# SparkFun_Qwiic_Micro_SAMD21E.net
KiCad netlist of a schematic drawn in EAGLE
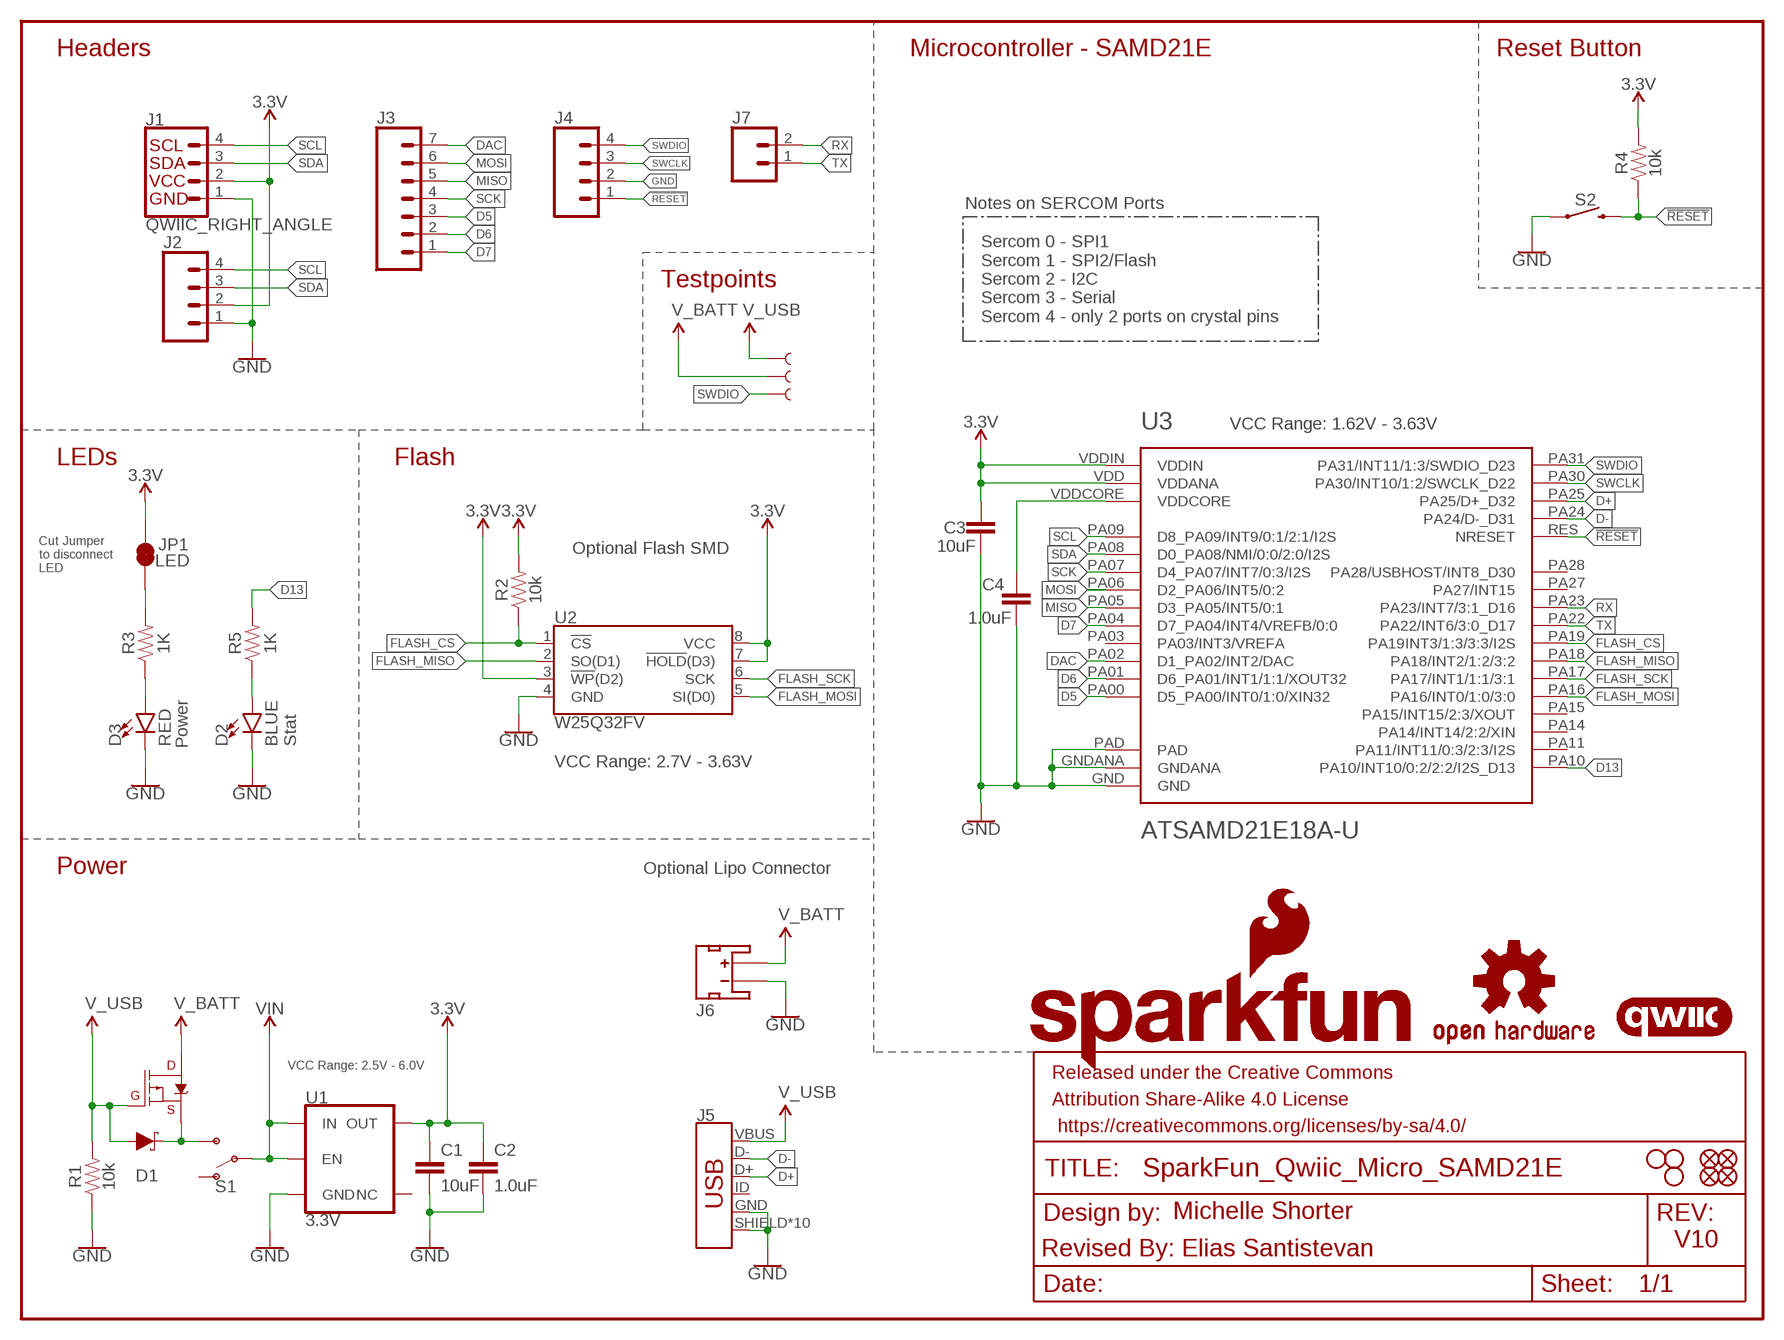
[diagram p0: schematic, sheet 1]

(export (version "E")
  (design (tool "Eeschema 10.0.6"))
  (components
    (comp (ref "C1")
      (value "10uF")
      (footprint "eagle-import:0603")
      (libsource (lib "eagle-import") (part "10UF-0603-6.3V-20%"))
    )
    (comp (ref "C2")
      (value "1.0uF")
      (footprint "eagle-import:0402")
      (libsource (lib "eagle-import") (part "1.0UF-0402-16V-10%"))
    )
    (comp (ref "C3")
      (value "10uF")
      (footprint "eagle-import:0603")
      (libsource (lib "eagle-import") (part "10UF-0603-6.3V-20%"))
    )
    (comp (ref "C4")
      (value "1.0uF")
      (footprint "eagle-import:0402")
      (libsource (lib "eagle-import") (part "1.0UF-0402-16V-10%"))
    )
    (comp (ref "D1")
      (value "1A/23V/620mV")
      (footprint "eagle-import:SOD-323")
      (libsource (lib "eagle-import") (part "DIODE-SCHOTTKY-BAT20J"))
    )
    (comp (ref "D2")
      (value "BLUE")
      (footprint "eagle-import:LED-0603")
      (libsource (lib "eagle-import") (part "LED-BLUE0603"))
    )
    (comp (ref "D3")
      (value "RED")
      (footprint "eagle-import:LED-0603")
      (libsource (lib "eagle-import") (part "LED-RED0603"))
    )
    (comp (ref "FD1")
      (value "FIDUCIALUFIDUCIAL")
      (footprint "eagle-import:FIDUCIAL-MICRO")
      (libsource (lib "eagle-import") (part "FIDUCIALUFIDUCIAL"))
    )
    (comp (ref "FD2")
      (value "FIDUCIALUFIDUCIAL")
      (footprint "eagle-import:FIDUCIAL-MICRO")
      (libsource (lib "eagle-import") (part "FIDUCIALUFIDUCIAL"))
    )
    (comp (ref "FD3")
      (value "FIDUCIALUFIDUCIAL")
      (footprint "eagle-import:FIDUCIAL-MICRO")
      (libsource (lib "eagle-import") (part "FIDUCIALUFIDUCIAL"))
    )
    (comp (ref "FD4")
      (value "FIDUCIALUFIDUCIAL")
      (footprint "eagle-import:FIDUCIAL-MICRO")
      (libsource (lib "eagle-import") (part "FIDUCIALUFIDUCIAL"))
    )
    (comp (ref "FRAME1")
      (value "FRAME-LETTER")
      (footprint "eagle-import:CREATIVE_COMMONS")
      (libsource (lib "eagle-import") (part "FRAME-LETTER"))
    )
    (comp (ref "H1")
      (value "STAND-OFF")
      (footprint "eagle-import:STAND-OFF")
      (libsource (lib "eagle-import") (part "STAND-OFF"))
    )
    (comp (ref "H2")
      (value "STAND-OFF")
      (footprint "eagle-import:STAND-OFF")
      (libsource (lib "eagle-import") (part "STAND-OFF"))
    )
    (comp (ref "H3")
      (value "STAND-OFF")
      (footprint "eagle-import:STAND-OFF")
      (libsource (lib "eagle-import") (part "STAND-OFF"))
    )
    (comp (ref "J1")
      (value "QWIIC_RIGHT_ANGLE")
      (footprint "eagle-import:JST04_1MM_RA")
      (libsource (lib "eagle-import") (part "QWIIC_CONNECTORJS-1MM"))
    )
    (comp (ref "J2")
      (value "CONN_041X04_NO_SILK")
      (footprint "eagle-import:1X04_NO_SILK")
      (libsource (lib "eagle-import") (part "CONN_041X04_NO_SILK"))
    )
    (comp (ref "J3")
      (value "CONN_07NO_SILK")
      (footprint "eagle-import:1X07_NO_SILK")
      (libsource (lib "eagle-import") (part "CONN_07NO_SILK"))
    )
    (comp (ref "J4")
      (value "CONN_041.27MM_NO_SILK")
      (footprint "eagle-import:1X04_1.27MM_NO_SILK")
      (libsource (lib "eagle-import") (part "CONN_041.27MM_NO_SILK"))
    )
    (comp (ref "J5")
      (value "USB_MICRO-B_HALF_PTH_MILL")
      (footprint "eagle-import:USB-MICROB-PTH-MILL")
      (libsource (lib "eagle-import") (part "USB_MICRO-B_HALF_PTH_MILL"))
    )
    (comp (ref "J6")
      (value "JST_2MM_MALE")
      (footprint "eagle-import:JST-2-SMD")
      (libsource (lib "eagle-import") (part "JST_2MM_MALE"))
    )
    (comp (ref "J7")
      (value "CONN_021X02_NO_SILK")
      (footprint "eagle-import:1X02_NO_SILK")
      (libsource (lib "eagle-import") (part "CONN_021X02_NO_SILK"))
    )
    (comp (ref "JP1")
      (value "LED")
      (footprint "eagle-import:SMT-JUMPER_2_NC_TRACE_SILK")
      (libsource (lib "eagle-import") (part "JUMPER-SMT_2_NC_TRACE_SILK"))
    )
    (comp (ref "LOGO1")
      (value "SFE_LOGO_NAME.1_INCH")
      (footprint "eagle-import:SFE_LOGO_NAME_.1")
      (libsource (lib "eagle-import") (part "SFE_LOGO_NAME.1_INCH"))
    )
    (comp (ref "LOGO2")
      (value "SFE_LOGO_FLAME.2_INCH")
      (footprint "eagle-import:SFE_LOGO_FLAME_.2")
      (libsource (lib "eagle-import") (part "SFE_LOGO_FLAME.2_INCH"))
    )
    (comp (ref "LOGO3")
      (value "OSHW-LOGOS")
      (footprint "eagle-import:OSHW-LOGO-S")
      (libsource (lib "eagle-import") (part "OSHW-LOGOS"))
    )
    (comp (ref "LOGO4")
      (value "QWIIC_LOGO_3MM")
      (footprint "eagle-import:QWIIC_3MM")
      (libsource (lib "eagle-import") (part "QWIIC_LOGO_3MM"))
    )
    (comp (ref "Q1")
      (value "3.1A/30V/105mΩ")
      (footprint "eagle-import:SOT23-3")
      (libsource (lib "eagle-import") (part "MOSFET_PCH-DMG2307L"))
    )
    (comp (ref "R1")
      (value "10k")
      (footprint "eagle-import:0402")
      (libsource (lib "eagle-import") (part "10KOHM-0402-1/16W-1%"))
    )
    (comp (ref "R2")
      (value "10k")
      (footprint "eagle-import:0402")
      (libsource (lib "eagle-import") (part "10KOHM-0402-1/16W-1%"))
    )
    (comp (ref "R3")
      (value "1K")
      (footprint "eagle-import:0402")
      (libsource (lib "eagle-import") (part "1KOHM-0402-1/16W-1%"))
    )
    (comp (ref "R4")
      (value "10k")
      (footprint "eagle-import:0402")
      (libsource (lib "eagle-import") (part "10KOHM-0402-1/16W-1%"))
    )
    (comp (ref "R5")
      (value "1K")
      (footprint "eagle-import:0402")
      (libsource (lib "eagle-import") (part "1KOHM-0402-1/16W-1%"))
    )
    (comp (ref "S1")
      (value "SWITCH-SPDT-SMD-RIGHT-ANGLE")
      (footprint "eagle-import:SWITCH_SPST_SMD_A")
      (libsource (lib "eagle-import") (part "SWITCH-SPDT-SMD-RIGHT-ANGLE"))
    )
    (comp (ref "S2")
      (value "MOMENTARY-SWITCH-SPST-SMD-4.6X2.8MM")
      (footprint "eagle-import:TACTILE_SWITCH_SMD_4.6X2.8MM")
      (libsource (lib "eagle-import") (part "MOMENTARY-SWITCH-SPST-SMD-4.6X2.8MM"))
    )
    (comp (ref "TP1")
      (value "TEST-POINTTP_15TH_THRU")
      (footprint "eagle-import:TP_15TH")
      (libsource (lib "eagle-import") (part "TEST-POINTTP_15TH_THRU"))
    )
    (comp (ref "TP2")
      (value "TEST-POINTTP_15TH_THRU")
      (footprint "eagle-import:TP_15TH")
      (libsource (lib "eagle-import") (part "TEST-POINTTP_15TH_THRU"))
    )
    (comp (ref "TP3")
      (value "TEST-POINTTP_15TH_THRU")
      (footprint "eagle-import:TP_15TH")
      (libsource (lib "eagle-import") (part "TEST-POINTTP_15TH_THRU"))
    )
    (comp (ref "U1")
      (value "3.3V")
      (footprint "eagle-import:SOT23-5")
      (libsource (lib "eagle-import") (part "V_REG_AP2112K-3.3V"))
    )
    (comp (ref "U2")
      (value "W25Q32FV")
      (footprint "eagle-import:SOIC-8")
      (libsource (lib "eagle-import") (part "W25Q32FVSS"))
    )
    (comp (ref "U3")
      (value "ATSAMD21E18A-U")
      (footprint "eagle-import:QFN-32_SAMD")
      (libsource (lib "eagle-import") (part "ATSAMD21E18A-U"))
    )
  )
  (nets
    (net (code "1") (name "/~{RESET}") (class "Default")
      (node (ref "J4") (pin "1") (pinfunction "1_1") (pintype "passive"))
      (node (ref "R4") (pin "1") (pinfunction "1_1") (pintype "passive"))
      (node (ref "S2") (pin "3") (pinfunction "2_3") (pintype "passive"))
      (node (ref "S2") (pin "4") (pinfunction "2_4") (pintype "passive"))
      (node (ref "U3") (pin "RES") (pinfunction "NRESET_RES") (pintype "bidirectional"))
    )
    (net (code "2") (name "3.3V") (class "Default")
      (node (ref "C1") (pin "1") (pinfunction "1_1") (pintype "passive"))
      (node (ref "C2") (pin "1") (pinfunction "1_1") (pintype "passive"))
      (node (ref "C3") (pin "1") (pinfunction "1_1") (pintype "passive"))
      (node (ref "J1") (pin "2") (pinfunction "2_2") (pintype "power_in"))
      (node (ref "J2") (pin "2") (pinfunction "2_2") (pintype "passive"))
      (node (ref "JP1") (pin "2") (pinfunction "2_2") (pintype "passive"))
      (node (ref "R2") (pin "2") (pinfunction "2_2") (pintype "passive"))
      (node (ref "R4") (pin "2") (pinfunction "2_2") (pintype "passive"))
      (node (ref "U1") (pin "5") (pinfunction "OUT_5") (pintype "passive"))
      (node (ref "U2") (pin "3") (pinfunction "~{WP}(D2)_3") (pintype "bidirectional"))
      (node (ref "U2") (pin "7") (pinfunction "~{HOLD}(D3)_7") (pintype "bidirectional"))
      (node (ref "U2") (pin "8") (pinfunction "VCC_8") (pintype "bidirectional"))
      (node (ref "U3") (pin "VDD") (pinfunction "VDDANA_VDD") (pintype "power_in"))
      (node (ref "U3") (pin "VDDIN") (pinfunction "VDDIN_VDDIN") (pintype "power_in"))
    )
    (net (code "3") (name "D+") (class "Default")
      (node (ref "J5") (pin "D+") (pinfunction "D+_D+") (pintype "bidirectional"))
      (node (ref "U3") (pin "PA25") (pinfunction "PA25/D+_D32_PA25") (pintype "bidirectional"))
    )
    (net (code "4") (name "D-") (class "Default")
      (node (ref "J5") (pin "D-") (pinfunction "D-_D-") (pintype "bidirectional"))
      (node (ref "U3") (pin "PA24") (pinfunction "PA24/D-_D31_PA24") (pintype "bidirectional"))
    )
    (net (code "5") (name "D5") (class "Default")
      (node (ref "J3") (pin "3") (pinfunction "3_3") (pintype "passive"))
      (node (ref "U3") (pin "PA00") (pinfunction "D5_PA00/INT0/1:0/XIN32_PA00") (pintype "bidirectional"))
    )
    (net (code "6") (name "D6") (class "Default")
      (node (ref "J3") (pin "2") (pinfunction "2_2") (pintype "passive"))
      (node (ref "U3") (pin "PA01") (pinfunction "D6_PA01/INT1/1:1/XOUT32_PA01") (pintype "bidirectional"))
    )
    (net (code "7") (name "D7") (class "Default")
      (node (ref "J3") (pin "1") (pinfunction "1_1") (pintype "passive"))
      (node (ref "U3") (pin "PA04") (pinfunction "D7_PA04/INT4/VREFB/0:0_PA04") (pintype "bidirectional"))
    )
    (net (code "8") (name "D13") (class "Default")
      (node (ref "R5") (pin "2") (pinfunction "2_2") (pintype "passive"))
      (node (ref "U3") (pin "PA10") (pinfunction "PA10/INT10/0:2/2:2/I2S_D13_PA10") (pintype "bidirectional"))
    )
    (net (code "9") (name "DAC") (class "Default")
      (node (ref "J3") (pin "7") (pinfunction "7_7") (pintype "passive"))
      (node (ref "U3") (pin "PA02") (pinfunction "D1_PA02/INT2/DAC_PA02") (pintype "bidirectional"))
    )
    (net (code "10") (name "FLASH_CS") (class "Default")
      (node (ref "R2") (pin "1") (pinfunction "1_1") (pintype "passive"))
      (node (ref "U2") (pin "1") (pinfunction "~{CS}_1") (pintype "bidirectional"))
      (node (ref "U3") (pin "PA19") (pinfunction "PA19INT3/1:3/3:3/I2S_PA19") (pintype "bidirectional"))
    )
    (net (code "11") (name "FLASH_MISO") (class "Default")
      (node (ref "U2") (pin "2") (pinfunction "SO(D1)_2") (pintype "bidirectional"))
      (node (ref "U3") (pin "PA18") (pinfunction "PA18/INT2/1:2/3:2_PA18") (pintype "bidirectional"))
    )
    (net (code "12") (name "FLASH_MOSI") (class "Default")
      (node (ref "U2") (pin "5") (pinfunction "SI(D0)_5") (pintype "bidirectional"))
      (node (ref "U3") (pin "PA16") (pinfunction "PA16/INT0/1:0/3:0_PA16") (pintype "bidirectional"))
    )
    (net (code "13") (name "FLASH_SCK") (class "Default")
      (node (ref "U2") (pin "6") (pinfunction "SCK_6") (pintype "bidirectional"))
      (node (ref "U3") (pin "PA17") (pinfunction "PA17/INT1/1:1/3:1_PA17") (pintype "bidirectional"))
    )
    (net (code "14") (name "GND") (class "Default")
      (node (ref "C1") (pin "2") (pinfunction "2_2") (pintype "passive"))
      (node (ref "C2") (pin "2") (pinfunction "2_2") (pintype "passive"))
      (node (ref "C3") (pin "2") (pinfunction "2_2") (pintype "passive"))
      (node (ref "C4") (pin "1") (pinfunction "1_1") (pintype "passive"))
      (node (ref "D2") (pin "C") (pinfunction "C_C") (pintype "passive"))
      (node (ref "D3") (pin "C") (pinfunction "C_C") (pintype "passive"))
      (node (ref "J1") (pin "1") (pinfunction "1_1") (pintype "power_in"))
      (node (ref "J2") (pin "1") (pinfunction "1_1") (pintype "passive"))
      (node (ref "J4") (pin "2") (pinfunction "2_2") (pintype "passive"))
      (node (ref "J5") (pin "GND") (pinfunction "GND_GND") (pintype "power_in"))
      (node (ref "J5") (pin "SHIELD") (pinfunction "SHIELD_SHIELD") (pintype "bidirectional"))
      (node (ref "J5") (pin "SHIELD10") (pinfunction "SHIELD_SHIELD10") (pintype "bidirectional"))
      (node (ref "J5") (pin "SHIELD2") (pinfunction "SHIELD_SHIELD2") (pintype "bidirectional"))
      (node (ref "J5") (pin "SHIELD3") (pinfunction "SHIELD_SHIELD3") (pintype "bidirectional"))
      (node (ref "J5") (pin "SHIELD4") (pinfunction "SHIELD_SHIELD4") (pintype "bidirectional"))
      (node (ref "J5") (pin "SHIELD5") (pinfunction "SHIELD_SHIELD5") (pintype "bidirectional"))
      (node (ref "J5") (pin "SHIELD6") (pinfunction "SHIELD_SHIELD6") (pintype "bidirectional"))
      (node (ref "J5") (pin "SHIELD7") (pinfunction "SHIELD_SHIELD7") (pintype "bidirectional"))
      (node (ref "J5") (pin "SHIELD8") (pinfunction "SHIELD_SHIELD8") (pintype "bidirectional"))
      (node (ref "J5") (pin "SHIELD9") (pinfunction "SHIELD_SHIELD9") (pintype "bidirectional"))
      (node (ref "J6") (pin "1") (pinfunction "-_1") (pintype "bidirectional"))
      (node (ref "R1") (pin "1") (pinfunction "1_1") (pintype "passive"))
      (node (ref "S2") (pin "1") (pinfunction "1_1") (pintype "passive"))
      (node (ref "S2") (pin "2") (pinfunction "1_2") (pintype "passive"))
      (node (ref "U1") (pin "2") (pinfunction "GND_2") (pintype "input"))
      (node (ref "U2") (pin "4") (pinfunction "GND_4") (pintype "bidirectional"))
      (node (ref "U3") (pin "GND") (pinfunction "GND_GND") (pintype "power_in"))
      (node (ref "U3") (pin "GNDANA") (pinfunction "GNDANA_GNDANA") (pintype "power_in"))
      (node (ref "U3") (pin "PAD") (pinfunction "PAD_PAD") (pintype "power_in"))
    )
    (net (code "15") (name "MISO") (class "Default")
      (node (ref "J3") (pin "5") (pinfunction "5_5") (pintype "passive"))
      (node (ref "U3") (pin "PA05") (pinfunction "D3_PA05/INT5/0:1_PA05") (pintype "bidirectional"))
    )
    (net (code "16") (name "MOSI") (class "Default")
      (node (ref "J3") (pin "6") (pinfunction "6_6") (pintype "passive"))
      (node (ref "U3") (pin "PA06") (pinfunction "D2_PA06/INT5/0:2_PA06") (pintype "bidirectional"))
    )
    (net (code "17") (name "Net-(C4-Pad2)") (class "Default")
      (node (ref "C4") (pin "2") (pinfunction "2_2") (pintype "passive"))
      (node (ref "U3") (pin "VDDCORE") (pinfunction "VDDCORE_VDDCORE") (pintype "power_in"))
    )
    (net (code "18") (name "Net-(D2-PadA)") (class "Default")
      (node (ref "D2") (pin "A") (pinfunction "A_A") (pintype "passive"))
      (node (ref "R5") (pin "1") (pinfunction "1_1") (pintype "passive"))
    )
    (net (code "19") (name "Net-(D3-PadA)") (class "Default")
      (node (ref "D3") (pin "A") (pinfunction "A_A") (pintype "passive"))
      (node (ref "R3") (pin "1") (pinfunction "1_1") (pintype "passive"))
    )
    (net (code "20") (name "Net-(JP1-Pad1)") (class "Default")
      (node (ref "JP1") (pin "1") (pinfunction "1_1") (pintype "passive"))
      (node (ref "R3") (pin "2") (pinfunction "2_2") (pintype "passive"))
    )
    (net (code "21") (name "Net-(Q1-S)") (class "Default")
      (node (ref "D1") (pin "C") (pinfunction "C_C") (pintype "passive"))
      (node (ref "Q1") (pin "2") (pinfunction "S_2") (pintype "bidirectional"))
      (node (ref "S1") (pin "3") (pinfunction "S_3") (pintype "passive"))
    )
    (net (code "22") (name "RX") (class "Default")
      (node (ref "J7") (pin "2") (pinfunction "2_2") (pintype "passive"))
      (node (ref "U3") (pin "PA23") (pinfunction "PA23/INT7/3:1_D16_PA23") (pintype "bidirectional"))
    )
    (net (code "23") (name "SCK") (class "Default")
      (node (ref "J3") (pin "4") (pinfunction "4_4") (pintype "passive"))
      (node (ref "U3") (pin "PA07") (pinfunction "D4_PA07/INT7/0:3/I2S_PA07") (pintype "bidirectional"))
    )
    (net (code "24") (name "SCL") (class "Default")
      (node (ref "J1") (pin "4") (pinfunction "4_4") (pintype "passive"))
      (node (ref "J2") (pin "4") (pinfunction "4_4") (pintype "passive"))
      (node (ref "U3") (pin "PA09") (pinfunction "D8_PA09/INT9/0:1/2:1/I2S_PA09") (pintype "bidirectional"))
    )
    (net (code "25") (name "SDA") (class "Default")
      (node (ref "J1") (pin "3") (pinfunction "3_3") (pintype "passive"))
      (node (ref "J2") (pin "3") (pinfunction "3_3") (pintype "passive"))
      (node (ref "U3") (pin "PA08") (pinfunction "D0_PA08/NMI/0:0/2:0/I2S_PA08") (pintype "bidirectional"))
    )
    (net (code "26") (name "SWCLK") (class "Default")
      (node (ref "J4") (pin "3") (pinfunction "3_3") (pintype "passive"))
      (node (ref "U3") (pin "PA30") (pinfunction "PA30/INT10/1:2/SWCLK_D22_PA30") (pintype "bidirectional"))
    )
    (net (code "27") (name "SWDIO") (class "Default")
      (node (ref "J4") (pin "4") (pinfunction "4_4") (pintype "passive"))
      (node (ref "TP3") (pin "P$1") (pinfunction "1_P$1") (pintype "bidirectional"))
      (node (ref "U3") (pin "PA31") (pinfunction "PA31/INT11/1:3/SWDIO_D23_PA31") (pintype "bidirectional"))
    )
    (net (code "28") (name "TX") (class "Default")
      (node (ref "J7") (pin "1") (pinfunction "1_1") (pintype "passive"))
      (node (ref "U3") (pin "PA22") (pinfunction "PA22/INT6/3:0_D17_PA22") (pintype "bidirectional"))
    )
    (net (code "29") (name "VIN") (class "Default")
      (node (ref "S1") (pin "2") (pinfunction "P_2") (pintype "passive"))
      (node (ref "U1") (pin "1") (pinfunction "IN_1") (pintype "input"))
      (node (ref "U1") (pin "3") (pinfunction "EN_3") (pintype "input"))
    )
    (net (code "30") (name "V_BATT") (class "Default")
      (node (ref "J6") (pin "2") (pinfunction "+_2") (pintype "bidirectional"))
      (node (ref "Q1") (pin "3") (pinfunction "D_3") (pintype "bidirectional"))
      (node (ref "TP2") (pin "P$1") (pinfunction "1_P$1") (pintype "bidirectional"))
    )
    (net (code "31") (name "V_USB") (class "Default")
      (node (ref "D1") (pin "A") (pinfunction "A_A") (pintype "passive"))
      (node (ref "J5") (pin "VBUS") (pinfunction "VBUS_VBUS") (pintype "power_in"))
      (node (ref "Q1") (pin "1") (pinfunction "G_1") (pintype "bidirectional"))
      (node (ref "R1") (pin "2") (pinfunction "2_2") (pintype "passive"))
      (node (ref "TP1") (pin "P$1") (pinfunction "1_P$1") (pintype "bidirectional"))
    )
    (net (code "32") (name "unconnected-(J5-PadID)") (class "Default")
      (node (ref "J5") (pin "ID") (pinfunction "ID_ID") (pintype "bidirectional"))
    )
    (net (code "33") (name "unconnected-(J6-PAD1-PadNC1)") (class "Default")
      (node (ref "J6") (pin "NC1") (pinfunction "PAD1_NC1") (pintype "bidirectional"))
    )
    (net (code "34") (name "unconnected-(J6-PAD2-PadNC2)") (class "Default")
      (node (ref "J6") (pin "NC2") (pinfunction "PAD2_NC2") (pintype "bidirectional"))
    )
    (net (code "35") (name "unconnected-(S1-O-Pad1)") (class "Default")
      (node (ref "S1") (pin "1") (pinfunction "O_1") (pintype "passive"))
    )
    (net (code "36") (name "unconnected-(U1-NC-Pad4)") (class "Default")
      (node (ref "U1") (pin "4") (pinfunction "NC_4") (pintype "no_connect"))
    )
    (net (code "37") (name "unconnected-(U3-PA03{slash}INT3{slash}VREFA-PadPA03)") (class "Default")
      (node (ref "U3") (pin "PA03") (pinfunction "PA03/INT3/VREFA_PA03") (pintype "bidirectional"))
    )
    (net (code "38") (name "unconnected-(U3-PA11{slash}INT11{slash}0:3{slash}2:3{slash}I2S-PadPA11)") (class "Default")
      (node (ref "U3") (pin "PA11") (pinfunction "PA11/INT11/0:3/2:3/I2S_PA11") (pintype "bidirectional"))
    )
    (net (code "39") (name "unconnected-(U3-PA14{slash}INT14{slash}2:2{slash}XIN-PadPA14)") (class "Default")
      (node (ref "U3") (pin "PA14") (pinfunction "PA14/INT14/2:2/XIN_PA14") (pintype "bidirectional"))
    )
    (net (code "40") (name "unconnected-(U3-PA15{slash}INT15{slash}2:3{slash}XOUT-PadPA15)") (class "Default")
      (node (ref "U3") (pin "PA15") (pinfunction "PA15/INT15/2:3/XOUT_PA15") (pintype "bidirectional"))
    )
    (net (code "41") (name "unconnected-(U3-PA27{slash}INT15-PadPA27)") (class "Default")
      (node (ref "U3") (pin "PA27") (pinfunction "PA27/INT15_PA27") (pintype "bidirectional"))
    )
    (net (code "42") (name "unconnected-(U3-PA28{slash}USBHOST{slash}INT8_D30-PadPA28)") (class "Default")
      (node (ref "U3") (pin "PA28") (pinfunction "PA28/USBHOST/INT8_D30_PA28") (pintype "bidirectional"))
    )
  )
)
